# AND_Gate.net
KiCad netlist of a schematic drawn in EAGLE
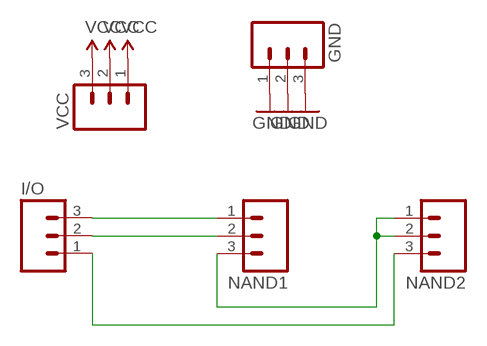
[diagram p0: schematic, sheet 1]

(export (version "E")
  (design (tool "Eeschema 10.0.6"))
  (components
    (comp (ref "GND")
      (value "M03LOCK")
      (footprint "eagle-import:1X03_LOCK")
      (libsource (lib "eagle-import") (part "M03LOCK"))
    )
    (comp (ref "I/O")
      (value "M03LOCK")
      (footprint "eagle-import:1X03_LOCK")
      (libsource (lib "eagle-import") (part "M03LOCK"))
    )
    (comp (ref "NAND1")
      (value "M03LOCK")
      (footprint "eagle-import:1X03_LOCK")
      (libsource (lib "eagle-import") (part "M03LOCK"))
    )
    (comp (ref "NAND2")
      (value "M03LOCK")
      (footprint "eagle-import:1X03_LOCK")
      (libsource (lib "eagle-import") (part "M03LOCK"))
    )
    (comp (ref "VCC")
      (value "M03LOCK")
      (footprint "eagle-import:1X03_LOCK")
      (libsource (lib "eagle-import") (part "M03LOCK"))
    )
  )
  (nets
    (net (code "1") (name "GND") (class "Default")
      (node (ref "GND") (pin "1") (pinfunction "1_1") (pintype "passive"))
      (node (ref "GND") (pin "2") (pinfunction "2_2") (pintype "passive"))
      (node (ref "GND") (pin "3") (pinfunction "3_3") (pintype "passive"))
    )
    (net (code "2") (name "Net-(I/O-Pad1)") (class "Default")
      (node (ref "I/O") (pin "1") (pinfunction "1_1") (pintype "passive"))
      (node (ref "NAND2") (pin "3") (pinfunction "3_3") (pintype "passive"))
    )
    (net (code "3") (name "Net-(I/O-Pad2)") (class "Default")
      (node (ref "I/O") (pin "2") (pinfunction "2_2") (pintype "passive"))
      (node (ref "NAND1") (pin "2") (pinfunction "2_2") (pintype "passive"))
    )
    (net (code "4") (name "Net-(I/O-Pad3)") (class "Default")
      (node (ref "I/O") (pin "3") (pinfunction "3_3") (pintype "passive"))
      (node (ref "NAND1") (pin "1") (pinfunction "1_1") (pintype "passive"))
    )
    (net (code "5") (name "Net-(NAND1-Pad3)") (class "Default")
      (node (ref "NAND1") (pin "3") (pinfunction "3_3") (pintype "passive"))
      (node (ref "NAND2") (pin "1") (pinfunction "1_1") (pintype "passive"))
      (node (ref "NAND2") (pin "2") (pinfunction "2_2") (pintype "passive"))
    )
    (net (code "6") (name "VCC") (class "Default")
      (node (ref "VCC") (pin "1") (pinfunction "1_1") (pintype "passive"))
      (node (ref "VCC") (pin "2") (pinfunction "2_2") (pintype "passive"))
      (node (ref "VCC") (pin "3") (pinfunction "3_3") (pintype "passive"))
    )
  )
)
